# USBTTL.net
KiCad netlist of a schematic drawn in Altium Designer
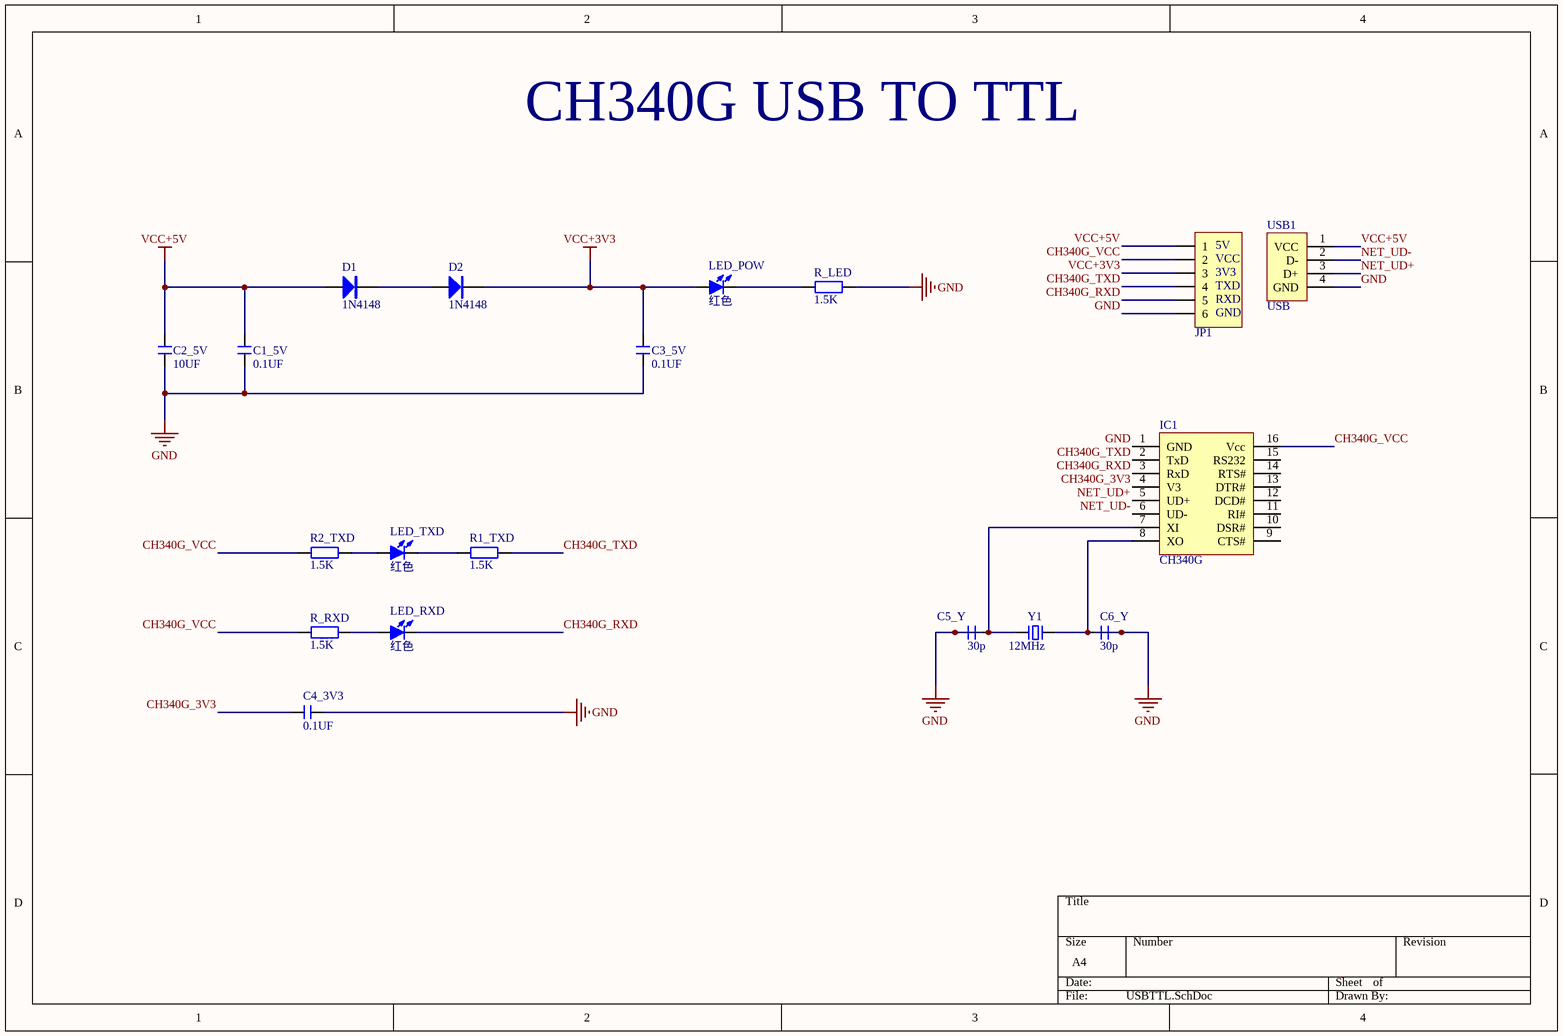
[diagram p0: USBTTL.SchDoc]

(export (version "E")
  (design (tool "Eeschema 10.0.6"))
  (components
    (comp (ref "C1_5V")
      (value "0.1UF")
      (footprint "C 0603")
      (description "无极性贴片电容")
      (fields (field (name "版权归属") "源创客"))
      (libsource (lib "电阻-电容-电感") (part "C"))
    )
    (comp (ref "C2_5V")
      (value "10UF")
      (footprint "C 0603")
      (description "无极性贴片电容")
      (fields (field (name "版权归属") "源创客"))
      (libsource (lib "电阻-电容-电感") (part "C"))
    )
    (comp (ref "C3_5V")
      (value "0.1UF")
      (footprint "C 0603")
      (description "无极性贴片电容")
      (fields (field (name "版权归属") "源创客"))
      (libsource (lib "电阻-电容-电感") (part "C"))
    )
    (comp (ref "C4_3V3")
      (value "0.1UF")
      (footprint "C 0603")
      (description "无极性贴片电容")
      (fields (field (name "版权归属") "源创客"))
      (libsource (lib "电阻-电容-电感") (part "C"))
    )
    (comp (ref "C5_Y")
      (value "30p")
      (footprint "C 0603")
      (description "无极性贴片电容")
      (fields (field (name "版权归属") "源创客"))
      (libsource (lib "电阻-电容-电感") (part "C"))
    )
    (comp (ref "C6_Y")
      (value "30p")
      (footprint "C 0603")
      (description "无极性贴片电容")
      (fields (field (name "版权归属") "源创客"))
      (libsource (lib "电阻-电容-电感") (part "C"))
    )
    (comp (ref "D1")
      (value "1N4148")
      (footprint "MINI_MELF (LL34)")
      (description "高速开关二极管")
      (fields (field (name "版权归属") "源创客"))
      (libsource (lib "二极管-整流桥") (part "1N4148"))
    )
    (comp (ref "D2")
      (value "1N4148")
      (footprint "MINI_MELF (LL34)")
      (description "高速开关二极管")
      (fields (field (name "版权归属") "源创客"))
      (libsource (lib "二极管-整流桥") (part "1N4148"))
    )
    (comp (ref "IC1")
      (value "CH340G")
      (footprint "SOP16_L")
      (description "串口转USB")
      (fields (field (name "版权归属") "源创客"))
      (libsource (lib "IC芯片") (part "CH340G"))
    )
    (comp (ref "JP1")
      (value "HDR-1X6")
      (footprint "HDR-1X6-USBTTL")
      (description "6P接插件")
      (fields (field (name "版权归属") "源创客"))
      (libsource (lib "接插件") (part "Header 6_USBTTL"))
    )
    (comp (ref "LED_POW")
      (value "红色")
      (footprint "LED 0603R")
      (description "贴片LED")
      (fields (field (name "版权归属") "源创客"))
      (libsource (lib "LED") (part "LED-SMD"))
    )
    (comp (ref "LED_RXD")
      (value "红色")
      (footprint "LED 0603R")
      (description "贴片LED")
      (fields (field (name "版权归属") "源创客"))
      (libsource (lib "LED") (part "LED-SMD"))
    )
    (comp (ref "LED_TXD")
      (value "红色")
      (footprint "LED 0603R")
      (description "贴片LED")
      (fields (field (name "版权归属") "源创客"))
      (libsource (lib "LED") (part "LED-SMD"))
    )
    (comp (ref "R1_TXD")
      (value "1.5K")
      (footprint "R 0603")
      (description "贴片电阻")
      (fields (field (name "版权归属") "源创客"))
      (libsource (lib "电阻-电容-电感") (part "R"))
    )
    (comp (ref "R2_TXD")
      (value "1.5K")
      (footprint "R 0603")
      (description "贴片电阻")
      (fields (field (name "版权归属") "源创客"))
      (libsource (lib "电阻-电容-电感") (part "R"))
    )
    (comp (ref "R_LED")
      (value "1.5K")
      (footprint "R 0603")
      (description "贴片电阻")
      (fields (field (name "版权归属") "源创客"))
      (libsource (lib "电阻-电容-电感") (part "R"))
    )
    (comp (ref "R_RXD")
      (value "1.5K")
      (footprint "R 0603")
      (description "贴片电阻")
      (fields (field (name "版权归属") "源创客"))
      (libsource (lib "电阻-电容-电感") (part "R"))
    )
    (comp (ref "USB1")
      (value "USB")
      (footprint "USB_A/P_A")
      (description "USB-A型公接口")
      (fields (field (name "版权归属") "源创客"))
      (libsource (lib "接口类") (part "USB-A/P"))
    )
    (comp (ref "Y1")
      (value "12MHz")
      (footprint "XTAL-49S DIP")
      (description "2脚晶振")
      (fields (field (name "版权归属") "源创客"))
      (libsource (lib "保险丝-晶振") (part "XTAL-2"))
    )
  )
  (nets
    (net (code "1") (name "/CH340G_3V3") (class "Default")
      (node (ref "C4_3V3") (pin "1") (pinfunction "1_1") (pintype "passive"))
      (node (ref "IC1") (pin "4") (pinfunction "V3_4") (pintype "passive"))
    )
    (net (code "2") (name "/CH340G_RXD") (class "Default")
      (node (ref "IC1") (pin "3") (pinfunction "RxD_3") (pintype "passive"))
      (node (ref "JP1") (pin "5") (pinfunction "5_5") (pintype "passive"))
      (node (ref "LED_RXD") (pin "2") (pinfunction "K_2") (pintype "passive"))
    )
    (net (code "3") (name "/CH340G_TXD") (class "Default")
      (node (ref "IC1") (pin "2") (pinfunction "TxD_2") (pintype "passive"))
      (node (ref "JP1") (pin "4") (pinfunction "4_4") (pintype "passive"))
      (node (ref "R1_TXD") (pin "2") (pinfunction "2_2") (pintype "passive"))
    )
    (net (code "4") (name "/CH340G_VCC") (class "Default")
      (node (ref "IC1") (pin "16") (pinfunction "Vcc_16") (pintype "passive"))
      (node (ref "JP1") (pin "2") (pinfunction "2_2") (pintype "passive"))
      (node (ref "R2_TXD") (pin "1") (pinfunction "1_1") (pintype "passive"))
      (node (ref "R_RXD") (pin "1") (pinfunction "1_1") (pintype "passive"))
    )
    (net (code "5") (name "/NET_UD+") (class "Default")
      (node (ref "IC1") (pin "5") (pinfunction "UD+_5") (pintype "passive"))
      (node (ref "USB1") (pin "3") (pinfunction "D+_3") (pintype "passive"))
    )
    (net (code "6") (name "/NET_UD-") (class "Default")
      (node (ref "IC1") (pin "6") (pinfunction "UD-_6") (pintype "passive"))
      (node (ref "USB1") (pin "2") (pinfunction "D-_2") (pintype "passive"))
    )
    (net (code "7") (name "GND") (class "Default")
      (node (ref "C1_5V") (pin "1") (pinfunction "1_1") (pintype "passive"))
      (node (ref "C2_5V") (pin "1") (pinfunction "1_1") (pintype "passive"))
      (node (ref "C3_5V") (pin "1") (pinfunction "1_1") (pintype "passive"))
      (node (ref "C4_3V3") (pin "2") (pinfunction "2_2") (pintype "passive"))
      (node (ref "C5_Y") (pin "1") (pinfunction "1_1") (pintype "passive"))
      (node (ref "C6_Y") (pin "2") (pinfunction "2_2") (pintype "passive"))
      (node (ref "IC1") (pin "1") (pinfunction "GND_1") (pintype "passive"))
      (node (ref "JP1") (pin "6") (pinfunction "6_6") (pintype "passive"))
      (node (ref "R_LED") (pin "2") (pinfunction "2_2") (pintype "passive"))
      (node (ref "USB1") (pin "4") (pinfunction "GND_4") (pintype "passive"))
    )
    (net (code "8") (name "Net-(D1-K)") (class "Default")
      (node (ref "D1") (pin "2") (pinfunction "K_2") (pintype "passive"))
      (node (ref "D2") (pin "1") (pinfunction "A_1") (pintype "passive"))
    )
    (net (code "9") (name "Net-(IC1-XI)") (class "Default")
      (node (ref "C5_Y") (pin "2") (pinfunction "2_2") (pintype "passive"))
      (node (ref "IC1") (pin "7") (pinfunction "XI_7") (pintype "passive"))
      (node (ref "Y1") (pin "1") (pinfunction "1_1") (pintype "passive"))
    )
    (net (code "10") (name "Net-(IC1-XO)") (class "Default")
      (node (ref "C6_Y") (pin "1") (pinfunction "1_1") (pintype "passive"))
      (node (ref "IC1") (pin "8") (pinfunction "XO_8") (pintype "passive"))
      (node (ref "Y1") (pin "2") (pinfunction "2_2") (pintype "passive"))
    )
    (net (code "11") (name "Net-(LED_POW-K)") (class "Default")
      (node (ref "LED_POW") (pin "2") (pinfunction "K_2") (pintype "passive"))
      (node (ref "R_LED") (pin "1") (pinfunction "1_1") (pintype "passive"))
    )
    (net (code "12") (name "Net-(LED_RXD-A)") (class "Default")
      (node (ref "LED_RXD") (pin "1") (pinfunction "A_1") (pintype "passive"))
      (node (ref "R_RXD") (pin "2") (pinfunction "2_2") (pintype "passive"))
    )
    (net (code "13") (name "Net-(LED_TXD-A)") (class "Default")
      (node (ref "LED_TXD") (pin "1") (pinfunction "A_1") (pintype "passive"))
      (node (ref "R2_TXD") (pin "2") (pinfunction "2_2") (pintype "passive"))
    )
    (net (code "14") (name "Net-(LED_TXD-K)") (class "Default")
      (node (ref "LED_TXD") (pin "2") (pinfunction "K_2") (pintype "passive"))
      (node (ref "R1_TXD") (pin "1") (pinfunction "1_1") (pintype "passive"))
    )
    (net (code "15") (name "VCC+3V3") (class "Default")
      (node (ref "C3_5V") (pin "2") (pinfunction "2_2") (pintype "passive"))
      (node (ref "D2") (pin "2") (pinfunction "K_2") (pintype "passive"))
      (node (ref "JP1") (pin "3") (pinfunction "3_3") (pintype "passive"))
      (node (ref "LED_POW") (pin "1") (pinfunction "A_1") (pintype "passive"))
    )
    (net (code "16") (name "VCC+5V") (class "Default")
      (node (ref "C1_5V") (pin "2") (pinfunction "2_2") (pintype "passive"))
      (node (ref "C2_5V") (pin "2") (pinfunction "2_2") (pintype "passive"))
      (node (ref "D1") (pin "1") (pinfunction "A_1") (pintype "passive"))
      (node (ref "JP1") (pin "1") (pinfunction "1_1") (pintype "passive"))
      (node (ref "USB1") (pin "1") (pinfunction "VCC_1") (pintype "passive"))
    )
    (net (code "17") (name "unconnected-(IC1-CTS#-Pad9)") (class "Default")
      (node (ref "IC1") (pin "9") (pinfunction "CTS#_9") (pintype "passive"))
    )
    (net (code "18") (name "unconnected-(IC1-DCD#-Pad12)") (class "Default")
      (node (ref "IC1") (pin "12") (pinfunction "DCD#_12") (pintype "passive"))
    )
    (net (code "19") (name "unconnected-(IC1-DSR#-Pad10)") (class "Default")
      (node (ref "IC1") (pin "10") (pinfunction "DSR#_10") (pintype "passive"))
    )
    (net (code "20") (name "unconnected-(IC1-DTR#-Pad13)") (class "Default")
      (node (ref "IC1") (pin "13") (pinfunction "DTR#_13") (pintype "passive"))
    )
    (net (code "21") (name "unconnected-(IC1-RI#-Pad11)") (class "Default")
      (node (ref "IC1") (pin "11") (pinfunction "RI#_11") (pintype "passive"))
    )
    (net (code "22") (name "unconnected-(IC1-RS232-Pad15)") (class "Default")
      (node (ref "IC1") (pin "15") (pinfunction "RS232_15") (pintype "passive"))
    )
    (net (code "23") (name "unconnected-(IC1-RTS#-Pad14)") (class "Default")
      (node (ref "IC1") (pin "14") (pinfunction "RTS#_14") (pintype "passive"))
    )
  )
)
